# main.net
KiCad netlist of a schematic drawn in Altium Designer
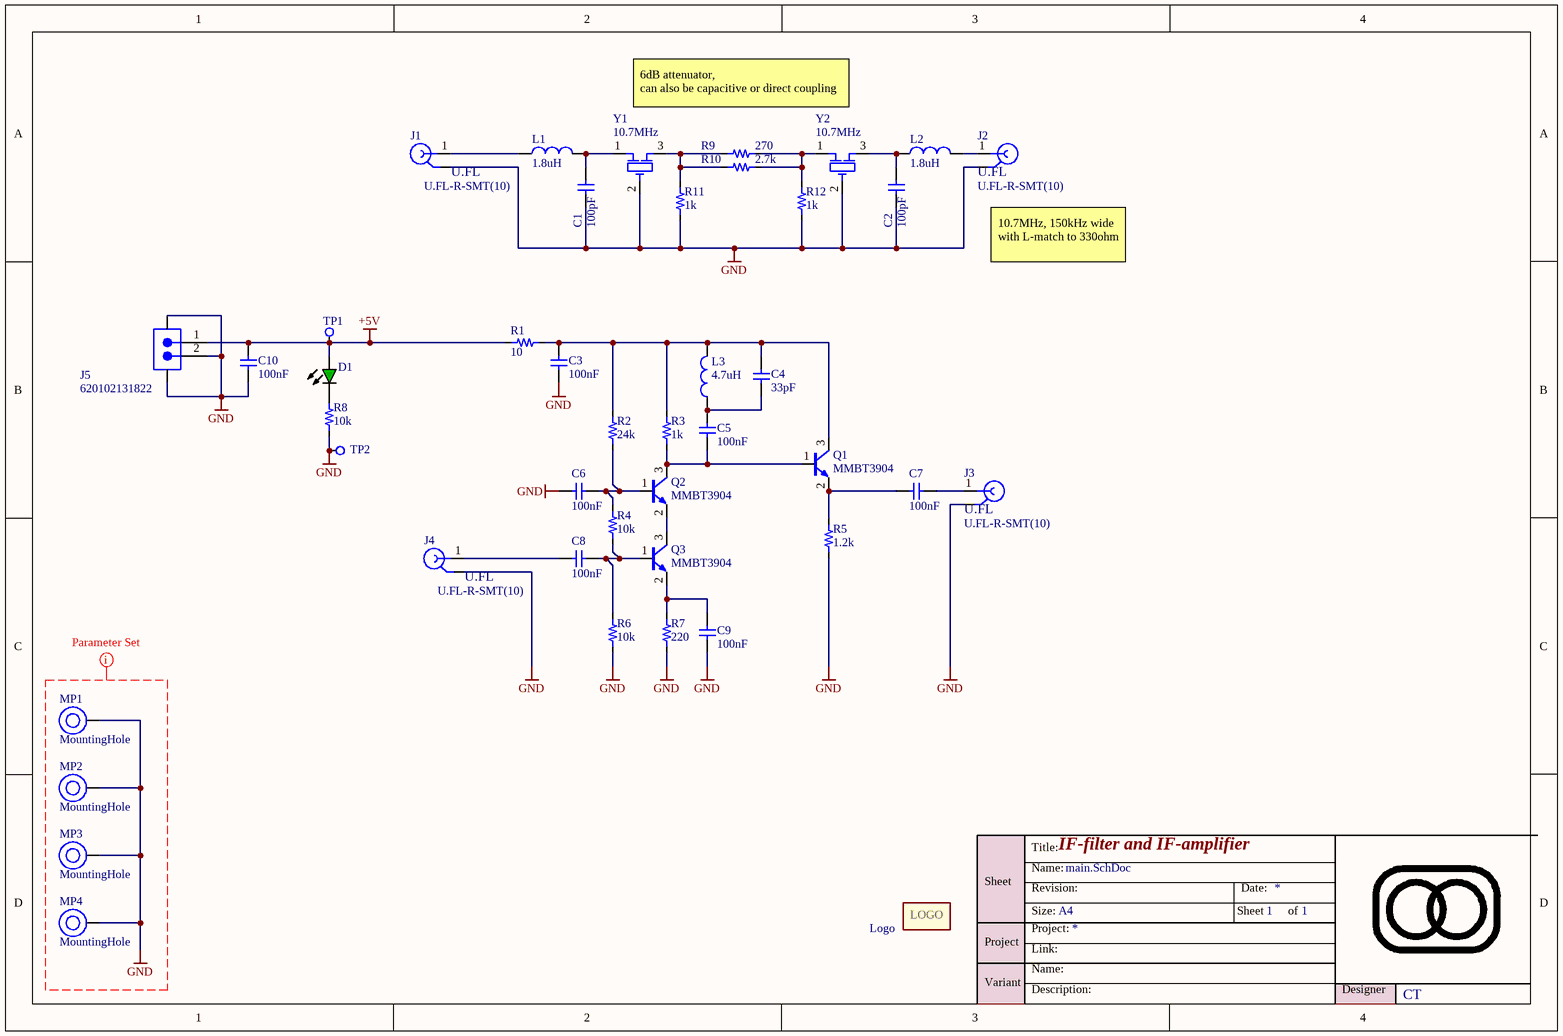
[diagram p0: main.SchDoc]

(export (version "E")
  (design (tool "Eeschema 10.0.6"))
  (components
    (comp (ref "C1")
      (value "100pF")
      (footprint "0603-C-N")
      (description "WCAP-CSGP Multilayer Ceramic Chip Capacitor, General Purpose, size 0603, NP0, 100pF, 50VDC")
      (fields (field (name "TOLERANCE") "5%") (field (name "PAGE PART #") "CCQJ101"))
      (libsource (lib "7c7 Engineering") (part "CAP-NP-2"))
    )
    (comp (ref "C2")
      (value "100pF")
      (footprint "0603-C-N")
      (description "WCAP-CSGP Multilayer Ceramic Chip Capacitor, General Purpose, size 0603, NP0, 100pF, 50VDC")
      (fields (field (name "TOLERANCE") "5%") (field (name "PAGE PART #") "CCQJ101"))
      (libsource (lib "7c7 Engineering") (part "CAP-NP-2"))
    )
    (comp (ref "C3")
      (value "100nF")
      (footprint "0603-C-N")
      (description "Capacitor MLCC, General Purpose, size 0603, X7R, 100nF, +/-10%, 50V")
      (fields (field (name "JLCPCB PART #") "C14663") (field (name "TOLERANCE") "10%"))
      (libsource (lib "7c7 Engineering") (part "CAP-NP-2"))
    )
    (comp (ref "C4")
      (value "33pF")
      (footprint "0603-C-N")
      (description "WCAP-CSGP Multilayer Ceramic Chip Capacitor, General Purpose, size 0603, NP0, 33pF, 50VDC")
      (fields (field (name "TOLERANCE") "5%") (field (name "JLCPCB BASIC PART") "Yes"))
      (libsource (lib "7c7 Engineering") (part "CAP-NP-2"))
    )
    (comp (ref "C5")
      (value "100nF")
      (footprint "0603-C-N")
      (description "Capacitor MLCC, General Purpose, size 0603, X7R, 100nF, +/-10%, 50V")
      (fields (field (name "JLCPCB PART #") "C14663") (field (name "TOLERANCE") "10%"))
      (libsource (lib "7c7 Engineering") (part "CAP-NP-2"))
    )
    (comp (ref "C6")
      (value "100nF")
      (footprint "0603-C-N")
      (description "Capacitor MLCC, General Purpose, size 0603, X7R, 100nF, +/-10%, 50V")
      (fields (field (name "JLCPCB PART #") "C14663") (field (name "TOLERANCE") "10%"))
      (libsource (lib "7c7 Engineering") (part "CAP-NP-2"))
    )
    (comp (ref "C7")
      (value "100nF")
      (footprint "0603-C-N")
      (description "Capacitor MLCC, General Purpose, size 0603, X7R, 100nF, +/-10%, 50V")
      (fields (field (name "JLCPCB PART #") "C14663") (field (name "TOLERANCE") "10%"))
      (libsource (lib "7c7 Engineering") (part "CAP-NP-2"))
    )
    (comp (ref "C8")
      (value "100nF")
      (footprint "0603-C-N")
      (description "Capacitor MLCC, General Purpose, size 0603, X7R, 100nF, +/-10%, 50V")
      (fields (field (name "JLCPCB PART #") "C14663") (field (name "TOLERANCE") "10%"))
      (libsource (lib "7c7 Engineering") (part "CAP-NP-2"))
    )
    (comp (ref "C9")
      (value "100nF")
      (footprint "0603-C-N")
      (description "Capacitor MLCC, General Purpose, size 0603, X7R, 100nF, +/-10%, 50V")
      (fields (field (name "JLCPCB PART #") "C14663") (field (name "TOLERANCE") "10%"))
      (libsource (lib "7c7 Engineering") (part "CAP-NP-2"))
    )
    (comp (ref "C10")
      (value "100nF")
      (footprint "0603-C-N")
      (description "Capacitor MLCC, General Purpose, size 0603, X7R, 100nF, +/-10%, 50V")
      (fields (field (name "TOLERANCE") "10%") (field (name "PAGE PART #") "CCQK104"))
      (libsource (lib "7c7 Engineering") (part "CAP-NP-2"))
    )
    (comp (ref "D1")
      (value "150060GS84000")
      (footprint "WL-SMCW_0603_150060xx8x000")
      (description "WL-SMCW Mono-color Chip LED Waterclear, size 0603, Green, 3.3V, 40°")
      (fields (field (name "JLCPCB PART #") "C7429914") (field (name "MANUFACTURER") "Wurth Elektronik"))
      (libsource (lib "7c7 Engineering") (part "LED-GREEN-2"))
    )
    (comp (ref "GR1")
      (value "Logo")
      (footprint "LOGO_9x6mm")
      (libsource (lib "Integrated_Library_LieBtrau") (part "Logo"))
    )
    (comp (ref "J1")
      (value "U.FL-R-SMT(10)")
      (footprint "HRS-U.FL-R-SMT_V")
      (fields (field (name "JLCPCB PART #") "C88373") (field (name "MANUFACTURER") "Hirose Electric"))
      (libsource (lib "7c7 Engineering") (part "CN_COAX"))
    )
    (comp (ref "J2")
      (value "U.FL-R-SMT(10)")
      (footprint "HRS-U.FL-R-SMT_V")
      (fields (field (name "JLCPCB PART #") "C88373") (field (name "MANUFACTURER") "Hirose Electric"))
      (libsource (lib "") (part "CN_COAX_1"))
    )
    (comp (ref "J3")
      (value "U.FL-R-SMT(10)")
      (footprint "HRS-U.FL-R-SMT_V")
      (fields (field (name "JLCPCB PART #") "C88373") (field (name "MANUFACTURER") "Hirose Electric"))
      (libsource (lib "") (part "CN_COAX_1"))
    )
    (comp (ref "J4")
      (value "U.FL-R-SMT(10)")
      (footprint "HRS-U.FL-R-SMT_V")
      (fields (field (name "JLCPCB PART #") "C88373") (field (name "MANUFACTURER") "Hirose Electric"))
      (libsource (lib "7c7 Engineering") (part "CN_COAX"))
    )
    (comp (ref "J5")
      (value "620102131822")
      (footprint "620102131822")
      (description "WR-WTB SMT Male Horizontal Shrouded Header, pitch 2mm, 2p")
      (fields
        (field (name "JLCPCB PART #") "C295747")
        (field (name "PAGE PART #") "K620102131822")
        (field (name "PUBLISHER") "Wurth Elektronik")
      )
      (libsource (lib "7c7 Engineering") (part "HDR_2P_2MP"))
    )
    (comp (ref "L1")
      (value "1.8uH")
      (footprint "WE-KI_1008")
      (description "Ind Chip Unshielded Wirewound 1.8uH 2% 7.9MHz 39Q-Factor Ferrite 600mA 1008 T/R")
      (fields (field (name "TOLERANCE") "2%") (field (name "JLCPCB BASIC PART") "No"))
      (libsource (lib "7c7 Engineering") (part "IND"))
    )
    (comp (ref "L2")
      (value "1.8uH")
      (footprint "WE-KI_1008")
      (description "Ind Chip Unshielded Wirewound 1.8uH 2% 7.9MHz 39Q-Factor Ferrite 600mA 1008 T/R")
      (fields (field (name "TOLERANCE") "2%") (field (name "JLCPCB BASIC PART") "No"))
      (libsource (lib "7c7 Engineering") (part "IND"))
    )
    (comp (ref "L3")
      (value "4.7uH")
      (footprint "WE-KI_1008")
      (description "Inductor RF Wirewound 4.7uH 2% 7.9MHz 31Q-Factor Ferrite 0.4A 1.68Ohm DCR 1008 T/R")
      (fields (field (name "TOLERANCE") "2%") (field (name "JLCPCB BASIC PART") "No"))
      (libsource (lib "7c7 Engineering") (part "IND"))
    )
    (comp (ref "MP1")
      (value "MountingHole")
      (footprint "PTH-M3D6.5_VIA-RING")
      (libsource (lib "7c7 Engineering") (part "MECH_NO_BOM"))
    )
    (comp (ref "MP2")
      (value "MountingHole")
      (footprint "PTH-M3D6.5_VIA-RING")
      (libsource (lib "7c7 Engineering") (part "MECH_NO_BOM"))
    )
    (comp (ref "MP3")
      (value "MountingHole")
      (footprint "PTH-M3D6.5_VIA-RING")
      (libsource (lib "7c7 Engineering") (part "MECH_NO_BOM"))
    )
    (comp (ref "MP4")
      (value "MountingHole")
      (footprint "PTH-M3D6.5_VIA-RING")
      (libsource (lib "7c7 Engineering") (part "MECH_NO_BOM"))
    )
    (comp (ref "Q1")
      (value "MMBT3904")
      (footprint "SOT-23-3-N")
      (description "NPN General Purpose Amplifier, 40 V, 0.2 A, -55 to 150 degC, 3-Pin SOT23, RoHS, Tape and Reel")
      (fields (field (name "MANUFACTURER") "Fairchild Semiconductor") (field (name "POWER") "625mW"))
      (libsource (lib "7c7 Engineering") (part "BJT-NPN-BEC"))
    )
    (comp (ref "Q2")
      (value "MMBT3904")
      (footprint "SOT-23-3-N")
      (description "NPN General Purpose Amplifier, 40 V, 0.2 A, -55 to 150 degC, 3-Pin SOT23, RoHS, Tape and Reel")
      (fields (field (name "MANUFACTURER") "Fairchild Semiconductor") (field (name "POWER") "625mW"))
      (libsource (lib "7c7 Engineering") (part "BJT-NPN-BEC"))
    )
    (comp (ref "Q3")
      (value "MMBT3904")
      (footprint "SOT-23-3-N")
      (description "NPN General Purpose Amplifier, 40 V, 0.2 A, -55 to 150 degC, 3-Pin SOT23, RoHS, Tape and Reel")
      (fields (field (name "MANUFACTURER") "Fairchild Semiconductor") (field (name "POWER") "625mW"))
      (libsource (lib "7c7 Engineering") (part "BJT-NPN-BEC"))
    )
    (comp (ref "R1")
      (value "10")
      (footprint "0603-R-N")
      (description "Chip Resistor, Thick Film, General Purpose, 0603, 100mW, 50V, 10 Ohm, +/-1%")
      (fields (field (name "TOLERANCE") "1%") (field (name "JLCPCB PART #") "C22859"))
      (libsource (lib "7c7 Engineering") (part "RES"))
    )
    (comp (ref "R2")
      (value "24k")
      (footprint "0603-R-N")
      (description "Chip Resistor, Thick Film, General Purpose, 0603, 100mW, 50V, 24 kOhm, +/-1%")
      (fields (field (name "TOLERANCE") "1%") (field (name "JLCPCB BASIC PART") "Yes"))
      (libsource (lib "7c7 Engineering") (part "RES"))
    )
    (comp (ref "R3")
      (value "1k")
      (footprint "0603-R-N")
      (description "Chip Resistor, Thick Film, General Purpose, 0603, 100mW, 50V, 1 kOhm, +/-1%")
      (fields (field (name "JLCPCB PART #") "C21190") (field (name "TOLERANCE") "1%"))
      (libsource (lib "7c7 Engineering") (part "RES"))
    )
    (comp (ref "R4")
      (value "10k")
      (footprint "0603-R-N")
      (description "Chip Resistor, Thick Film, General Purpose, 0603, 100mW, 50V, 10 kOhm, +/-1%")
      (fields (field (name "FLIR PART #") "YRES10K-1") (field (name "PAGE PART #") "ROQF1002"))
      (libsource (lib "7c7 Engineering") (part "RES"))
    )
    (comp (ref "R5")
      (value "1.2k")
      (footprint "0603-R-N")
      (description "Chip Resistor, Thick Film, General Purpose, 0603, 100mW, 50V, 1.2 kOhm, +/-1%")
      (fields (field (name "TOLERANCE") "1%") (field (name "JLCPCB PART #") "C22765"))
      (libsource (lib "7c7 Engineering") (part "RES"))
    )
    (comp (ref "R6")
      (value "10k")
      (footprint "0603-R-N")
      (description "Chip Resistor, Thick Film, General Purpose, 0603, 100mW, 50V, 10 kOhm, +/-1%")
      (fields (field (name "FLIR PART #") "YRES10K-1") (field (name "PAGE PART #") "ROQF1002"))
      (libsource (lib "7c7 Engineering") (part "RES"))
    )
    (comp (ref "R7")
      (value "220")
      (footprint "0603-R-N")
      (description "Res Thick Film 0603 220 Ohm 1% 0.1W(1/10W) ±100ppm/C Pad SMD T/R Automotive AEC-Q200")
      (fields (field (name "TOLERANCE") "1%") (field (name "JLCPCB PART #") "C22962"))
      (libsource (lib "7c7 Engineering") (part "RES"))
    )
    (comp (ref "R8")
      (value "10k")
      (footprint "0603-R-N")
      (description "Chip Resistor, Thick Film, General Purpose, 0603, 100mW, 50V, 10 kOhm, +/-1%")
      (fields (field (name "FLIR PART #") "YRES10K-1") (field (name "PAGE PART #") "ROQF1002"))
      (libsource (lib "7c7 Engineering") (part "RES"))
    )
    (comp (ref "R9")
      (value "270")
      (footprint "0603-R-N")
      (description "Chip Resistor, Thick Film, General Purpose, 0603, 100mW, 50V, 270 Ohm, +/-1%")
      (fields (field (name "TOLERANCE") "1%") (field (name "JLCPCB PART #") "C22966"))
      (libsource (lib "7c7 Engineering") (part "RES"))
    )
    (comp (ref "R10")
      (value "2.7k")
      (footprint "0603-R-N")
      (description "Res Thick Film 0603 2.7K Ohm 1% 0.1W(1/10W) ±100ppm/C Pad SMD Automotive T/R")
      (fields (field (name "TOLERANCE") "1%") (field (name "JLCPCB PART #") "C13167"))
      (libsource (lib "7c7 Engineering") (part "RES"))
    )
    (comp (ref "R11")
      (value "1k")
      (footprint "0603-R-N")
      (description "Chip Resistor, Thick Film, General Purpose, 0603, 100mW, 50V, 1 kOhm, +/-1%")
      (fields (field (name "JLCPCB PART #") "C21190") (field (name "TOLERANCE") "1%"))
      (libsource (lib "7c7 Engineering") (part "RES"))
    )
    (comp (ref "R12")
      (value "1k")
      (footprint "0603-R-N")
      (description "Chip Resistor, Thick Film, General Purpose, 0603, 100mW, 50V, 1 kOhm, +/-1%")
      (fields (field (name "JLCPCB PART #") "C21190") (field (name "TOLERANCE") "1%"))
      (libsource (lib "7c7 Engineering") (part "RES"))
    )
    (comp (ref "TP1")
      (value "Testpad with multiple sizes")
      (footprint "TP_1.5mm_0.3mmHole")
      (description "Testpad land")
      (libsource (lib "7c7 Engineering") (part "Testpad"))
    )
    (comp (ref "TP2")
      (value "Testpad with multiple sizes")
      (footprint "TP_1.5mm_0.3mmHole")
      (description "Testpad land")
      (libsource (lib "7c7 Engineering") (part "Testpad"))
    )
    (comp (ref "Y1")
      (value "SFECV10M7JA00-R0")
      (footprint "FP-SFECV10M7JA00-R0-MFG")
      (description "SFECV Series 10.7 MHz 2 Element 150 kHz Bw 330 Ohm Surface Mount Ceramic Filter")
      (fields (field (name "FREQUENCY") "10.7MHz"))
      (libsource (lib "7c7 Engineering") (part "XTAL-3"))
    )
    (comp (ref "Y2")
      (value "SFECV10M7JA00-R0")
      (footprint "FP-SFECV10M7JA00-R0-MFG")
      (description "SFECV Series 10.7 MHz 2 Element 150 kHz Bw 330 Ohm Surface Mount Ceramic Filter")
      (fields (field (name "FREQUENCY") "10.7MHz"))
      (libsource (lib "7c7 Engineering") (part "XTAL-3"))
    )
  )
  (nets
    (net (code "1") (name "+5V") (class "Default")
      (node (ref "C10") (pin "2") (pinfunction "2_2") (pintype "passive"))
      (node (ref "D1") (pin "2") (pinfunction "A_2") (pintype "passive"))
      (node (ref "J5") (pin "1") (pinfunction "1_1") (pintype "passive"))
      (node (ref "R1") (pin "2") (pinfunction "2_2") (pintype "passive"))
      (node (ref "TP1") (pin "1") (pinfunction "Pad_1") (pintype "passive"))
    )
    (net (code "2") (name "GND") (class "Default")
      (node (ref "C1") (pin "1") (pinfunction "1_1") (pintype "passive"))
      (node (ref "C10") (pin "1") (pinfunction "1_1") (pintype "passive"))
      (node (ref "C2") (pin "1") (pinfunction "1_1") (pintype "passive"))
      (node (ref "C3") (pin "1") (pinfunction "1_1") (pintype "passive"))
      (node (ref "C6") (pin "2") (pinfunction "2_2") (pintype "passive"))
      (node (ref "C9") (pin "1") (pinfunction "1_1") (pintype "passive"))
      (node (ref "J1") (pin "2") (pinfunction "GND_2") (pintype "passive"))
      (node (ref "J2") (pin "2") (pinfunction "GND_2") (pintype "passive"))
      (node (ref "J3") (pin "2") (pinfunction "GND_2") (pintype "passive"))
      (node (ref "J4") (pin "2") (pinfunction "GND_2") (pintype "passive"))
      (node (ref "J5") (pin "2") (pinfunction "2_2") (pintype "passive"))
      (node (ref "J5") (pin "MP1") (pinfunction "MP1_MP1") (pintype "passive"))
      (node (ref "J5") (pin "MP2") (pinfunction "MP2_MP2") (pintype "passive"))
      (node (ref "MP1") (pin "1") (pinfunction "H1_1") (pintype "passive"))
      (node (ref "MP2") (pin "1") (pinfunction "H1_1") (pintype "passive"))
      (node (ref "MP3") (pin "1") (pinfunction "H1_1") (pintype "passive"))
      (node (ref "MP4") (pin "1") (pinfunction "H1_1") (pintype "passive"))
      (node (ref "R11") (pin "1") (pinfunction "1_1") (pintype "passive"))
      (node (ref "R12") (pin "1") (pinfunction "1_1") (pintype "passive"))
      (node (ref "R5") (pin "1") (pinfunction "1_1") (pintype "passive"))
      (node (ref "R6") (pin "1") (pinfunction "1_1") (pintype "passive"))
      (node (ref "R7") (pin "1") (pinfunction "1_1") (pintype "passive"))
      (node (ref "R8") (pin "1") (pinfunction "1_1") (pintype "passive"))
      (node (ref "TP2") (pin "1") (pinfunction "Pad_1") (pintype "passive"))
      (node (ref "Y1") (pin "2") (pinfunction "2_2") (pintype "passive"))
      (node (ref "Y2") (pin "2") (pinfunction "2_2") (pintype "passive"))
    )
    (net (code "3") (name "Net-(C1-Pad2)") (class "Default")
      (node (ref "C1") (pin "2") (pinfunction "2_2") (pintype "passive"))
      (node (ref "L1") (pin "2") (pinfunction "2_2") (pintype "passive"))
      (node (ref "Y1") (pin "1") (pinfunction "1_1") (pintype "passive"))
    )
    (net (code "4") (name "Net-(C2-Pad2)") (class "Default")
      (node (ref "C2") (pin "2") (pinfunction "2_2") (pintype "passive"))
      (node (ref "L2") (pin "1") (pinfunction "1_1") (pintype "passive"))
      (node (ref "Y2") (pin "3") (pinfunction "3_3") (pintype "passive"))
    )
    (net (code "5") (name "Net-(C4-Pad1)") (class "Default")
      (node (ref "C4") (pin "1") (pinfunction "1_1") (pintype "passive"))
      (node (ref "C5") (pin "1") (pinfunction "1_1") (pintype "passive"))
      (node (ref "L3") (pin "1") (pinfunction "1_1") (pintype "passive"))
    )
    (net (code "6") (name "Net-(D1-K)") (class "Default")
      (node (ref "D1") (pin "1") (pinfunction "K_1") (pintype "passive"))
      (node (ref "R8") (pin "2") (pinfunction "2_2") (pintype "passive"))
    )
    (net (code "7") (name "Net-(J1-SIG)") (class "Default")
      (node (ref "J1") (pin "1") (pinfunction "SIG_1") (pintype "passive"))
      (node (ref "L1") (pin "1") (pinfunction "1_1") (pintype "passive"))
    )
    (net (code "8") (name "Net-(J2-SIG)") (class "Default")
      (node (ref "J2") (pin "1") (pinfunction "SIG_1") (pintype "passive"))
      (node (ref "L2") (pin "2") (pinfunction "2_2") (pintype "passive"))
    )
    (net (code "9") (name "Net-(J3-SIG)") (class "Default")
      (node (ref "C7") (pin "1") (pinfunction "1_1") (pintype "passive"))
      (node (ref "J3") (pin "1") (pinfunction "SIG_1") (pintype "passive"))
    )
    (net (code "10") (name "Net-(J4-SIG)") (class "Default")
      (node (ref "C8") (pin "2") (pinfunction "2_2") (pintype "passive"))
      (node (ref "J4") (pin "1") (pinfunction "SIG_1") (pintype "passive"))
    )
    (net (code "11") (name "Net-(Q1-B)") (class "Default")
      (node (ref "C5") (pin "2") (pinfunction "2_2") (pintype "passive"))
      (node (ref "Q1") (pin "1") (pinfunction "B_1") (pintype "passive"))
      (node (ref "Q2") (pin "3") (pinfunction "C_3") (pintype "passive"))
      (node (ref "R3") (pin "1") (pinfunction "1_1") (pintype "passive"))
    )
    (net (code "12") (name "Net-(Q1-C)") (class "Default")
      (node (ref "C3") (pin "2") (pinfunction "2_2") (pintype "passive"))
      (node (ref "C4") (pin "2") (pinfunction "2_2") (pintype "passive"))
      (node (ref "L3") (pin "2") (pinfunction "2_2") (pintype "passive"))
      (node (ref "Q1") (pin "3") (pinfunction "C_3") (pintype "passive"))
      (node (ref "R1") (pin "1") (pinfunction "1_1") (pintype "passive"))
      (node (ref "R2") (pin "2") (pinfunction "2_2") (pintype "passive"))
      (node (ref "R3") (pin "2") (pinfunction "2_2") (pintype "passive"))
    )
    (net (code "13") (name "Net-(Q1-E)") (class "Default")
      (node (ref "C7") (pin "2") (pinfunction "2_2") (pintype "passive"))
      (node (ref "Q1") (pin "2") (pinfunction "E_2") (pintype "passive"))
      (node (ref "R5") (pin "2") (pinfunction "2_2") (pintype "passive"))
    )
    (net (code "14") (name "Net-(Q2-B)") (class "Default")
      (node (ref "C6") (pin "1") (pinfunction "1_1") (pintype "passive"))
      (node (ref "Q2") (pin "1") (pinfunction "B_1") (pintype "passive"))
      (node (ref "R2") (pin "1") (pinfunction "1_1") (pintype "passive"))
      (node (ref "R4") (pin "2") (pinfunction "2_2") (pintype "passive"))
    )
    (net (code "15") (name "Net-(Q2-E)") (class "Default")
      (node (ref "Q2") (pin "2") (pinfunction "E_2") (pintype "passive"))
      (node (ref "Q3") (pin "3") (pinfunction "C_3") (pintype "passive"))
    )
    (net (code "16") (name "Net-(Q3-B)") (class "Default")
      (node (ref "C8") (pin "1") (pinfunction "1_1") (pintype "passive"))
      (node (ref "Q3") (pin "1") (pinfunction "B_1") (pintype "passive"))
      (node (ref "R4") (pin "1") (pinfunction "1_1") (pintype "passive"))
      (node (ref "R6") (pin "2") (pinfunction "2_2") (pintype "passive"))
    )
    (net (code "17") (name "Net-(Q3-E)") (class "Default")
      (node (ref "C9") (pin "2") (pinfunction "2_2") (pintype "passive"))
      (node (ref "Q3") (pin "2") (pinfunction "E_2") (pintype "passive"))
      (node (ref "R7") (pin "2") (pinfunction "2_2") (pintype "passive"))
    )
    (net (code "18") (name "Net-(R10-Pad1)") (class "Default")
      (node (ref "R10") (pin "1") (pinfunction "1_1") (pintype "passive"))
      (node (ref "R11") (pin "2") (pinfunction "2_2") (pintype "passive"))
      (node (ref "R9") (pin "1") (pinfunction "1_1") (pintype "passive"))
      (node (ref "Y1") (pin "3") (pinfunction "3_3") (pintype "passive"))
    )
    (net (code "19") (name "Net-(R10-Pad2)") (class "Default")
      (node (ref "R10") (pin "2") (pinfunction "2_2") (pintype "passive"))
      (node (ref "R12") (pin "2") (pinfunction "2_2") (pintype "passive"))
      (node (ref "R9") (pin "2") (pinfunction "2_2") (pintype "passive"))
      (node (ref "Y2") (pin "1") (pinfunction "1_1") (pintype "passive"))
    )
  )
)
